# Serial_Load_Cell_converter.net
KiCad netlist of a schematic drawn in EAGLE
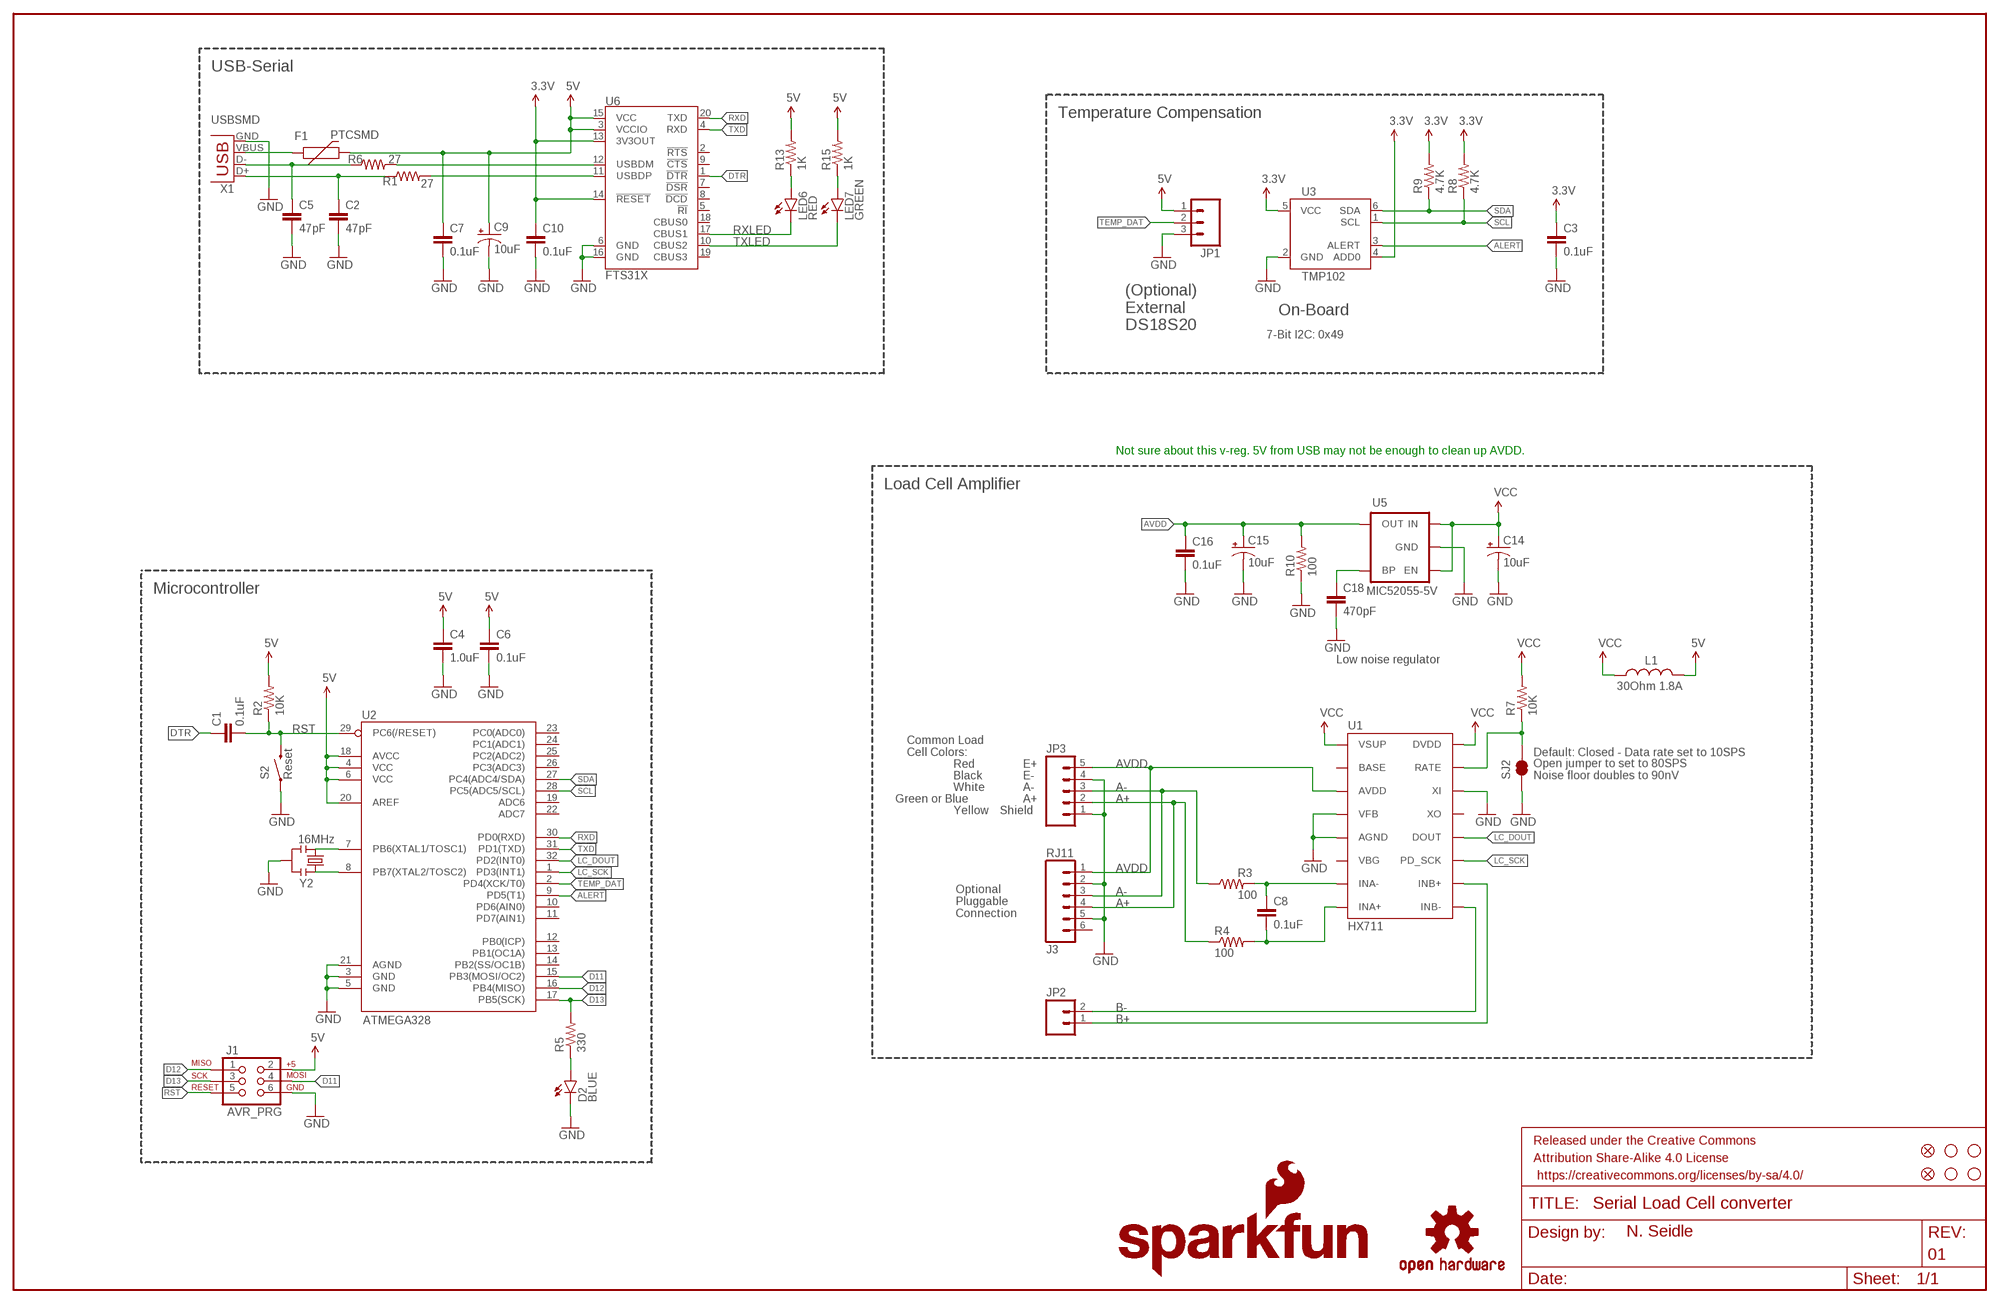
[diagram p0: schematic, sheet 1]

(export (version "E")
  (design (tool "Eeschema 10.0.6"))
  (components
    (comp (ref "C1")
      (value "0.1uF")
      (footprint "eagle-import:0603-CAP")
      (libsource (lib "eagle-import") (part "0.1UF-25V(+80/-20%)(0603)"))
    )
    (comp (ref "C2")
      (value "47pF")
      (footprint "eagle-import:0603-CAP")
      (libsource (lib "eagle-import") (part "47PF-50V-5%(0603)"))
    )
    (comp (ref "C3")
      (value "0.1uF")
      (footprint "eagle-import:0603-CAP")
      (libsource (lib "eagle-import") (part "0.1UF-25V-5%(0603)"))
    )
    (comp (ref "C4")
      (value "1.0uF")
      (footprint "eagle-import:0603-CAP")
      (libsource (lib "eagle-import") (part "1.0UF-16V-10%(0603)"))
    )
    (comp (ref "C5")
      (value "47pF")
      (footprint "eagle-import:0603-CAP")
      (libsource (lib "eagle-import") (part "47PF-50V-5%(0603)"))
    )
    (comp (ref "C6")
      (value "0.1uF")
      (footprint "eagle-import:0603-CAP")
      (libsource (lib "eagle-import") (part "0.1UF-25V(+80/-20%)(0603)"))
    )
    (comp (ref "C7")
      (value "0.1uF")
      (footprint "eagle-import:0603-CAP")
      (libsource (lib "eagle-import") (part "0.1UF-25V(+80/-20%)(0603)"))
    )
    (comp (ref "C8")
      (value "0.1uF")
      (footprint "eagle-import:0603-CAP")
      (libsource (lib "eagle-import") (part "0.1UF-25V-5%(0603)"))
    )
    (comp (ref "C9")
      (value "10uF")
      (footprint "eagle-import:EIA3216")
      (libsource (lib "eagle-import") (part "10UF-16V-10%(TANT)"))
    )
    (comp (ref "C10")
      (value "0.1uF")
      (footprint "eagle-import:0603-CAP")
      (libsource (lib "eagle-import") (part "0.1UF-25V(+80/-20%)(0603)"))
    )
    (comp (ref "C14")
      (value "10uF")
      (footprint "eagle-import:EIA3216")
      (libsource (lib "eagle-import") (part "10UF-16V-10%(TANT)"))
    )
    (comp (ref "C15")
      (value "10uF")
      (footprint "eagle-import:EIA3216")
      (libsource (lib "eagle-import") (part "10UF-16V-10%(TANT)"))
    )
    (comp (ref "C16")
      (value "0.1uF")
      (footprint "eagle-import:0603-CAP")
      (libsource (lib "eagle-import") (part "0.1UF-25V-5%(0603)"))
    )
    (comp (ref "C18")
      (value "470pF")
      (footprint "eagle-import:0603-CAP")
      (libsource (lib "eagle-import") (part "470PF-50V-5%(0603)SMD"))
    )
    (comp (ref "D2")
      (value "BLUE")
      (footprint "eagle-import:LED-1206")
      (libsource (lib "eagle-import") (part "LED-BLUE1206"))
    )
    (comp (ref "F1")
      (value "PTCSMD")
      (footprint "eagle-import:PTC-1206")
      (libsource (lib "eagle-import") (part "PTCSMD"))
    )
    (comp (ref "FID1")
      (value "FIDUCIAL1X2")
      (footprint "eagle-import:FIDUCIAL-1X2")
      (libsource (lib "eagle-import") (part "FIDUCIAL1X2"))
    )
    (comp (ref "FID2")
      (value "FIDUCIAL1X2")
      (footprint "eagle-import:FIDUCIAL-1X2")
      (libsource (lib "eagle-import") (part "FIDUCIAL1X2"))
    )
    (comp (ref "FRAME1")
      (value "FRAME-LEDGER")
      (footprint "eagle-import:CREATIVE_COMMONS")
      (fields (field (name "DESIGNER") "N. Seidle") (field (name "VERSION") "01"))
      (libsource (lib "eagle-import") (part "FRAME-LEDGER"))
    )
    (comp (ref "J1")
      (value "AVR_PRG")
      (footprint "eagle-import:2X3")
      (libsource (lib "eagle-import") (part "AVR_SPI_PRG_6PTH"))
    )
    (comp (ref "J3")
      (value "RJ11")
      (footprint "eagle-import:RJ11-6")
      (libsource (lib "eagle-import") (part "RJ11-6PTH"))
    )
    (comp (ref "JP1")
      (value "M03PTH")
      (footprint "eagle-import:1X03")
      (libsource (lib "eagle-import") (part "M03PTH"))
    )
    (comp (ref "JP2")
      (value "M02PTH")
      (footprint "eagle-import:1X02")
      (libsource (lib "eagle-import") (part "M02PTH"))
    )
    (comp (ref "JP3")
      (value "M05PTH")
      (footprint "eagle-import:1X05")
      (libsource (lib "eagle-import") (part "M05PTH"))
    )
    (comp (ref "L1")
      (value "30Ohm 1.8A")
      (footprint "eagle-import:0603")
      (libsource (lib "eagle-import") (part "INDUCTOR30OHM,1.8A"))
    )
    (comp (ref "LED6")
      (value "RED")
      (footprint "eagle-import:LED-1206")
      (libsource (lib "eagle-import") (part "LED-RED1206"))
    )
    (comp (ref "LED7")
      (value "GREEN")
      (footprint "eagle-import:LED-1206")
      (libsource (lib "eagle-import") (part "LED-GREENLARGE"))
    )
    (comp (ref "LOGO1")
      (value "SFE_LOGO_NAME_FLAME.1_INCH")
      (footprint "eagle-import:SFE_LOGO_NAME_FLAME_.1")
      (libsource (lib "eagle-import") (part "SFE_LOGO_NAME_FLAME.1_INCH"))
    )
    (comp (ref "LOGO2")
      (value "OSHW-LOGOS")
      (footprint "eagle-import:OSHW-LOGO-S")
      (libsource (lib "eagle-import") (part "OSHW-LOGOS"))
    )
    (comp (ref "LOGO4")
      (value "SFE_LOGO_NAME_FLAME.1_INCH")
      (footprint "eagle-import:SFE_LOGO_NAME_FLAME_.1")
      (libsource (lib "eagle-import") (part "SFE_LOGO_NAME_FLAME.1_INCH"))
    )
    (comp (ref "R1")
      (value "27")
      (footprint "eagle-import:0603")
      (libsource (lib "eagle-import") (part "27OHM1/10W1%(0603)"))
    )
    (comp (ref "R2")
      (value "10K")
      (footprint "eagle-import:0603-RES")
      (libsource (lib "eagle-import") (part "10KOHM-1/10W-1%(0603)0603"))
    )
    (comp (ref "R3")
      (value "100")
      (footprint "eagle-import:0603-RES")
      (libsource (lib "eagle-import") (part "100OHM-1/10W-1%(0603)"))
    )
    (comp (ref "R4")
      (value "100")
      (footprint "eagle-import:0603-RES")
      (libsource (lib "eagle-import") (part "100OHM-1/10W-1%(0603)"))
    )
    (comp (ref "R5")
      (value "330")
      (footprint "eagle-import:0603-RES")
      (libsource (lib "eagle-import") (part "330OHM1/10W1%(0603)"))
    )
    (comp (ref "R6")
      (value "27")
      (footprint "eagle-import:0603")
      (libsource (lib "eagle-import") (part "27OHM1/10W1%(0603)"))
    )
    (comp (ref "R7")
      (value "10K")
      (footprint "eagle-import:0603-RES")
      (libsource (lib "eagle-import") (part "10KOHM-1/10W-1%(0603)0603"))
    )
    (comp (ref "R8")
      (value "4.7K")
      (footprint "eagle-import:0603-RES")
      (libsource (lib "eagle-import") (part "4.7KOHM-1/10W-1%(0603)"))
    )
    (comp (ref "R9")
      (value "4.7K")
      (footprint "eagle-import:0603-RES")
      (libsource (lib "eagle-import") (part "4.7KOHM-1/10W-1%(0603)"))
    )
    (comp (ref "R10")
      (value "100")
      (footprint "eagle-import:0603-RES")
      (libsource (lib "eagle-import") (part "100OHM-1/10W-1%(0603)"))
    )
    (comp (ref "R13")
      (value "1K")
      (footprint "eagle-import:0603-RES")
      (libsource (lib "eagle-import") (part "1KOHM-1/10W-1%(0603)"))
    )
    (comp (ref "R15")
      (value "1K")
      (footprint "eagle-import:0603-RES")
      (libsource (lib "eagle-import") (part "1KOHM-1/10W-1%(0603)"))
    )
    (comp (ref "S2")
      (value "Reset")
      (footprint "eagle-import:TACTILE-SWITCH-SMD")
      (libsource (lib "eagle-import") (part "SWITCH-MOMENTARY-2SMD"))
    )
    (comp (ref "SJ2")
      (value "JUMPER-PAD-2-NC_BY_TRACE")
      (footprint "eagle-import:PAD-JUMPER-2-NC_BY_TRACE_YES_SILK")
      (libsource (lib "eagle-import") (part "JUMPER-PAD-2-NC_BY_TRACE"))
    )
    (comp (ref "STANDOFF1")
      (value "STAND-OFF")
      (footprint "eagle-import:STAND-OFF")
      (libsource (lib "eagle-import") (part "STAND-OFF"))
    )
    (comp (ref "STANDOFF2")
      (value "STAND-OFF")
      (footprint "eagle-import:STAND-OFF")
      (libsource (lib "eagle-import") (part "STAND-OFF"))
    )
    (comp (ref "STANDOFF3")
      (value "STAND-OFF")
      (footprint "eagle-import:STAND-OFF")
      (libsource (lib "eagle-import") (part "STAND-OFF"))
    )
    (comp (ref "STANDOFF4")
      (value "STAND-OFF")
      (footprint "eagle-import:STAND-OFF")
      (libsource (lib "eagle-import") (part "STAND-OFF"))
    )
    (comp (ref "U1")
      (value "HX711")
      (footprint "eagle-import:SO16")
      (libsource (lib "eagle-import") (part "HX711HX711"))
    )
    (comp (ref "U2")
      (value "ATMEGA328")
      (footprint "eagle-import:TQFP32-08")
      (libsource (lib "eagle-import") (part "ATMEGA328_SMT"))
    )
    (comp (ref "U3")
      (value "TMP102")
      (footprint "eagle-import:SOT563")
      (libsource (lib "eagle-import") (part "TMP102"))
    )
    (comp (ref "U5")
      (value "MIC52055-5V")
      (footprint "eagle-import:SOT23-5")
      (libsource (lib "eagle-import") (part "MIC52055V"))
    )
    (comp (ref "U6")
      (value "FTS31X")
      (footprint "eagle-import:SSOP20_L")
      (libsource (lib "eagle-import") (part "FT231XS"))
    )
    (comp (ref "X1")
      (value "USBSMD")
      (footprint "eagle-import:USB-MINIB")
      (libsource (lib "eagle-import") (part "USBSMD"))
    )
    (comp (ref "Y2")
      (value "16MHz")
      (footprint "eagle-import:RESONATOR-SMD")
      (libsource (lib "eagle-import") (part "RESONATOR16MHZ"))
    )
  )
  (nets
    (net (code "1") (name "/A+") (class "Default")
      (node (ref "J3") (pin "4") (pinfunction "4_4") (pintype "passive"))
      (node (ref "JP3") (pin "2") (pinfunction "2_2") (pintype "passive"))
      (node (ref "R4") (pin "1") (pinfunction "1_1") (pintype "passive"))
    )
    (net (code "2") (name "/A-") (class "Default")
      (node (ref "J3") (pin "3") (pinfunction "3_3") (pintype "passive"))
      (node (ref "JP3") (pin "3") (pinfunction "3_3") (pintype "passive"))
      (node (ref "R3") (pin "1") (pinfunction "1_1") (pintype "passive"))
    )
    (net (code "3") (name "/B+") (class "Default")
      (node (ref "JP2") (pin "1") (pinfunction "1_1") (pintype "passive"))
      (node (ref "U1") (pin "10") (pinfunction "INB+_10") (pintype "bidirectional"))
    )
    (net (code "4") (name "/B-") (class "Default")
      (node (ref "JP2") (pin "2") (pinfunction "2_2") (pintype "passive"))
      (node (ref "U1") (pin "9") (pinfunction "INB-_9") (pintype "bidirectional"))
    )
    (net (code "5") (name "/RXLED") (class "Default")
      (node (ref "LED6") (pin "C") (pinfunction "C_C") (pintype "passive"))
      (node (ref "U6") (pin "17") (pinfunction "CBUS1_17") (pintype "bidirectional"))
    )
    (net (code "6") (name "/TXLED") (class "Default")
      (node (ref "LED7") (pin "C") (pinfunction "C_C") (pintype "passive"))
      (node (ref "U6") (pin "10") (pinfunction "CBUS2_10") (pintype "bidirectional"))
    )
    (net (code "7") (name "3.3V") (class "Default")
      (node (ref "C10") (pin "1") (pinfunction "1_1") (pintype "passive"))
      (node (ref "C3") (pin "1") (pinfunction "1_1") (pintype "passive"))
      (node (ref "R8") (pin "2") (pinfunction "2_2") (pintype "passive"))
      (node (ref "R9") (pin "2") (pinfunction "2_2") (pintype "passive"))
      (node (ref "U3") (pin "4") (pinfunction "ADD0_4") (pintype "bidirectional"))
      (node (ref "U3") (pin "5") (pinfunction "VCC_5") (pintype "bidirectional"))
      (node (ref "U6") (pin "13") (pinfunction "3V3OUT_13") (pintype "bidirectional"))
      (node (ref "U6") (pin "14") (pinfunction "~{RESET}_14") (pintype "bidirectional"))
    )
    (net (code "8") (name "5V") (class "Default")
      (node (ref "C4") (pin "1") (pinfunction "1_1") (pintype "passive"))
      (node (ref "C6") (pin "1") (pinfunction "1_1") (pintype "passive"))
      (node (ref "C7") (pin "1") (pinfunction "1_1") (pintype "passive"))
      (node (ref "C9") (pin "A") (pinfunction "+_A") (pintype "passive"))
      (node (ref "F1") (pin "2") (pinfunction "2_2") (pintype "bidirectional"))
      (node (ref "J1") (pin "2") (pinfunction "2_2") (pintype "passive"))
      (node (ref "JP1") (pin "1") (pinfunction "1_1") (pintype "passive"))
      (node (ref "L1") (pin "2") (pinfunction "2_2") (pintype "passive"))
      (node (ref "R13") (pin "2") (pinfunction "2_2") (pintype "passive"))
      (node (ref "R15") (pin "2") (pinfunction "2_2") (pintype "passive"))
      (node (ref "R2") (pin "2") (pinfunction "2_2") (pintype "passive"))
      (node (ref "U2") (pin "18") (pinfunction "AVCC_18") (pintype "bidirectional"))
      (node (ref "U2") (pin "20") (pinfunction "AREF_20") (pintype "bidirectional"))
      (node (ref "U2") (pin "4") (pinfunction "VCC_4") (pintype "bidirectional"))
      (node (ref "U2") (pin "6") (pinfunction "VCC_6") (pintype "bidirectional"))
      (node (ref "U6") (pin "15") (pinfunction "VCC_15") (pintype "bidirectional"))
      (node (ref "U6") (pin "3") (pinfunction "VCCIO_3") (pintype "bidirectional"))
    )
    (net (code "9") (name "ALERT") (class "Default")
      (node (ref "U2") (pin "9") (pinfunction "PD5(T1)_9") (pintype "bidirectional"))
      (node (ref "U3") (pin "3") (pinfunction "ALERT_3") (pintype "bidirectional"))
    )
    (net (code "10") (name "AVDD") (class "Default")
      (node (ref "C15") (pin "A") (pinfunction "+_A") (pintype "passive"))
      (node (ref "C16") (pin "1") (pinfunction "1_1") (pintype "passive"))
      (node (ref "J3") (pin "1") (pinfunction "1_1") (pintype "passive"))
      (node (ref "JP3") (pin "5") (pinfunction "5_5") (pintype "passive"))
      (node (ref "R10") (pin "2") (pinfunction "2_2") (pintype "passive"))
      (node (ref "U1") (pin "3") (pinfunction "AVDD_3") (pintype "bidirectional"))
      (node (ref "U5") (pin "5") (pinfunction "OUT_5") (pintype "passive"))
    )
    (net (code "11") (name "D11") (class "Default")
      (node (ref "J1") (pin "4") (pinfunction "4_4") (pintype "passive"))
      (node (ref "U2") (pin "15") (pinfunction "PB3(MOSI/OC2)_15") (pintype "bidirectional"))
    )
    (net (code "12") (name "D12") (class "Default")
      (node (ref "J1") (pin "1") (pinfunction "1_1") (pintype "passive"))
      (node (ref "U2") (pin "16") (pinfunction "PB4(MISO)_16") (pintype "bidirectional"))
    )
    (net (code "13") (name "D13") (class "Default")
      (node (ref "J1") (pin "3") (pinfunction "3_3") (pintype "passive"))
      (node (ref "R5") (pin "2") (pinfunction "2_2") (pintype "passive"))
      (node (ref "U2") (pin "17") (pinfunction "PB5(SCK)_17") (pintype "bidirectional"))
    )
    (net (code "14") (name "DTR") (class "Default")
      (node (ref "C1") (pin "1") (pinfunction "1_1") (pintype "passive"))
      (node (ref "U6") (pin "1") (pinfunction "~{DTR}_1") (pintype "bidirectional"))
    )
    (net (code "15") (name "GND") (class "Default")
      (node (ref "C10") (pin "2") (pinfunction "2_2") (pintype "passive"))
      (node (ref "C14") (pin "C") (pinfunction "-_C") (pintype "passive"))
      (node (ref "C15") (pin "C") (pinfunction "-_C") (pintype "passive"))
      (node (ref "C16") (pin "2") (pinfunction "2_2") (pintype "passive"))
      (node (ref "C18") (pin "2") (pinfunction "2_2") (pintype "passive"))
      (node (ref "C2") (pin "2") (pinfunction "2_2") (pintype "passive"))
      (node (ref "C3") (pin "2") (pinfunction "2_2") (pintype "passive"))
      (node (ref "C4") (pin "2") (pinfunction "2_2") (pintype "passive"))
      (node (ref "C5") (pin "2") (pinfunction "2_2") (pintype "passive"))
      (node (ref "C6") (pin "2") (pinfunction "2_2") (pintype "passive"))
      (node (ref "C7") (pin "2") (pinfunction "2_2") (pintype "passive"))
      (node (ref "C9") (pin "C") (pinfunction "-_C") (pintype "passive"))
      (node (ref "D2") (pin "C") (pinfunction "C_C") (pintype "passive"))
      (node (ref "J1") (pin "6") (pinfunction "6_6") (pintype "passive"))
      (node (ref "J3") (pin "2") (pinfunction "2_2") (pintype "passive"))
      (node (ref "J3") (pin "5") (pinfunction "5_5") (pintype "passive"))
      (node (ref "JP1") (pin "3") (pinfunction "3_3") (pintype "passive"))
      (node (ref "JP3") (pin "1") (pinfunction "1_1") (pintype "passive"))
      (node (ref "JP3") (pin "4") (pinfunction "4_4") (pintype "passive"))
      (node (ref "R10") (pin "1") (pinfunction "1_1") (pintype "passive"))
      (node (ref "S2") (pin "1") (pinfunction "1_1") (pintype "passive"))
      (node (ref "SJ2") (pin "1") (pinfunction "1_1") (pintype "passive"))
      (node (ref "U1") (pin "14") (pinfunction "XI_14") (pintype "bidirectional"))
      (node (ref "U1") (pin "4") (pinfunction "VFB_4") (pintype "bidirectional"))
      (node (ref "U1") (pin "5") (pinfunction "AGND_5") (pintype "bidirectional"))
      (node (ref "U2") (pin "21") (pinfunction "AGND_21") (pintype "bidirectional"))
      (node (ref "U2") (pin "3") (pinfunction "GND_3") (pintype "bidirectional"))
      (node (ref "U2") (pin "5") (pinfunction "GND_5") (pintype "bidirectional"))
      (node (ref "U3") (pin "2") (pinfunction "GND_2") (pintype "bidirectional"))
      (node (ref "U5") (pin "2") (pinfunction "GND_2") (pintype "input"))
      (node (ref "U6") (pin "16") (pinfunction "GND_16") (pintype "bidirectional"))
      (node (ref "U6") (pin "6") (pinfunction "GND_6") (pintype "bidirectional"))
      (node (ref "X1") (pin "GND") (pinfunction "GND_GND") (pintype "bidirectional"))
      (node (ref "Y2") (pin "2") (pinfunction "2_2") (pintype "passive"))
    )
    (net (code "16") (name "LC_DOUT") (class "Default")
      (node (ref "U1") (pin "12") (pinfunction "DOUT_12") (pintype "bidirectional"))
      (node (ref "U2") (pin "32") (pinfunction "PD2(INT0)_32") (pintype "bidirectional"))
    )
    (net (code "17") (name "LC_SCK") (class "Default")
      (node (ref "U1") (pin "11") (pinfunction "PD_SCK_11") (pintype "bidirectional"))
      (node (ref "U2") (pin "1") (pinfunction "PD3(INT1)_1") (pintype "bidirectional"))
    )
    (net (code "18") (name "Net-(C2-Pad1)") (class "Default")
      (node (ref "C2") (pin "1") (pinfunction "1_1") (pintype "passive"))
      (node (ref "R1") (pin "1") (pinfunction "1_1") (pintype "passive"))
      (node (ref "X1") (pin "D+") (pinfunction "D+_D+") (pintype "bidirectional"))
    )
    (net (code "19") (name "Net-(C5-Pad1)") (class "Default")
      (node (ref "C5") (pin "1") (pinfunction "1_1") (pintype "passive"))
      (node (ref "R6") (pin "1") (pinfunction "1_1") (pintype "passive"))
      (node (ref "X1") (pin "D-") (pinfunction "D-_D-") (pintype "bidirectional"))
    )
    (net (code "20") (name "Net-(D2-PadA)") (class "Default")
      (node (ref "D2") (pin "A") (pinfunction "A_A") (pintype "passive"))
      (node (ref "R5") (pin "1") (pinfunction "1_1") (pintype "passive"))
    )
    (net (code "21") (name "Net-(F1-Pad1)") (class "Default")
      (node (ref "F1") (pin "1") (pinfunction "1_1") (pintype "bidirectional"))
      (node (ref "X1") (pin "VBUS") (pinfunction "VBUS_VBUS") (pintype "bidirectional"))
    )
    (net (code "22") (name "Net-(LED6-PadA)") (class "Default")
      (node (ref "LED6") (pin "A") (pinfunction "A_A") (pintype "passive"))
      (node (ref "R13") (pin "1") (pinfunction "1_1") (pintype "passive"))
    )
    (net (code "23") (name "Net-(LED7-PadA)") (class "Default")
      (node (ref "LED7") (pin "A") (pinfunction "A_A") (pintype "passive"))
      (node (ref "R15") (pin "1") (pinfunction "1_1") (pintype "passive"))
    )
    (net (code "24") (name "Net-(U1-INA+)") (class "Default")
      (node (ref "C8") (pin "2") (pinfunction "2_2") (pintype "passive"))
      (node (ref "R4") (pin "2") (pinfunction "2_2") (pintype "passive"))
      (node (ref "U1") (pin "8") (pinfunction "INA+_8") (pintype "bidirectional"))
    )
    (net (code "25") (name "Net-(U1-INA-)") (class "Default")
      (node (ref "C8") (pin "1") (pinfunction "1_1") (pintype "passive"))
      (node (ref "R3") (pin "2") (pinfunction "2_2") (pintype "passive"))
      (node (ref "U1") (pin "7") (pinfunction "INA-_7") (pintype "bidirectional"))
    )
    (net (code "26") (name "Net-(U1-RATE)") (class "Default")
      (node (ref "R7") (pin "1") (pinfunction "1_1") (pintype "passive"))
      (node (ref "SJ2") (pin "2") (pinfunction "2_2") (pintype "passive"))
      (node (ref "U1") (pin "15") (pinfunction "RATE_15") (pintype "bidirectional"))
    )
    (net (code "27") (name "Net-(U2-PB6(XTAL1{slash}TOSC1))") (class "Default")
      (node (ref "U2") (pin "7") (pinfunction "PB6(XTAL1/TOSC1)_7") (pintype "bidirectional"))
      (node (ref "Y2") (pin "1") (pinfunction "1_1") (pintype "passive"))
    )
    (net (code "28") (name "Net-(U2-PB7(XTAL2{slash}TOSC2))") (class "Default")
      (node (ref "U2") (pin "8") (pinfunction "PB7(XTAL2/TOSC2)_8") (pintype "bidirectional"))
      (node (ref "Y2") (pin "3") (pinfunction "3_3") (pintype "passive"))
    )
    (net (code "29") (name "Net-(U5-BP)") (class "Default")
      (node (ref "C18") (pin "1") (pinfunction "1_1") (pintype "passive"))
      (node (ref "U5") (pin "4") (pinfunction "BP_4") (pintype "input"))
    )
    (net (code "30") (name "Net-(U6-USBDM)") (class "Default")
      (node (ref "R6") (pin "2") (pinfunction "2_2") (pintype "passive"))
      (node (ref "U6") (pin "12") (pinfunction "USBDM_12") (pintype "bidirectional"))
    )
    (net (code "31") (name "Net-(U6-USBDP)") (class "Default")
      (node (ref "R1") (pin "2") (pinfunction "2_2") (pintype "passive"))
      (node (ref "U6") (pin "11") (pinfunction "USBDP_11") (pintype "bidirectional"))
    )
    (net (code "32") (name "RST") (class "Default")
      (node (ref "C1") (pin "2") (pinfunction "2_2") (pintype "passive"))
      (node (ref "J1") (pin "5") (pinfunction "5_5") (pintype "passive"))
      (node (ref "R2") (pin "1") (pinfunction "1_1") (pintype "passive"))
      (node (ref "S2") (pin "3") (pinfunction "2_3") (pintype "passive"))
      (node (ref "U2") (pin "29") (pinfunction "PC6(/RESET)_29") (pintype "bidirectional"))
    )
    (net (code "33") (name "RXD") (class "Default")
      (node (ref "U2") (pin "30") (pinfunction "PD0(RXD)_30") (pintype "bidirectional"))
      (node (ref "U6") (pin "20") (pinfunction "TXD_20") (pintype "bidirectional"))
    )
    (net (code "34") (name "SCL") (class "Default")
      (node (ref "R8") (pin "1") (pinfunction "1_1") (pintype "passive"))
      (node (ref "U2") (pin "28") (pinfunction "PC5(ADC5/SCL)_28") (pintype "bidirectional"))
      (node (ref "U3") (pin "1") (pinfunction "SCL_1") (pintype "bidirectional"))
    )
    (net (code "35") (name "SDA") (class "Default")
      (node (ref "R9") (pin "1") (pinfunction "1_1") (pintype "passive"))
      (node (ref "U2") (pin "27") (pinfunction "PC4(ADC4/SDA)_27") (pintype "bidirectional"))
      (node (ref "U3") (pin "6") (pinfunction "SDA_6") (pintype "bidirectional"))
    )
    (net (code "36") (name "TEMP_DAT") (class "Default")
      (node (ref "JP1") (pin "2") (pinfunction "2_2") (pintype "passive"))
      (node (ref "U2") (pin "2") (pinfunction "PD4(XCK/T0)_2") (pintype "bidirectional"))
    )
    (net (code "37") (name "TXD") (class "Default")
      (node (ref "U2") (pin "31") (pinfunction "PD1(TXD)_31") (pintype "bidirectional"))
      (node (ref "U6") (pin "4") (pinfunction "RXD_4") (pintype "bidirectional"))
    )
    (net (code "38") (name "VCC") (class "Default")
      (node (ref "C14") (pin "A") (pinfunction "+_A") (pintype "passive"))
      (node (ref "L1") (pin "1") (pinfunction "1_1") (pintype "passive"))
      (node (ref "R7") (pin "2") (pinfunction "2_2") (pintype "passive"))
      (node (ref "U1") (pin "1") (pinfunction "VSUP_1") (pintype "bidirectional"))
      (node (ref "U1") (pin "16") (pinfunction "DVDD_16") (pintype "bidirectional"))
      (node (ref "U5") (pin "1") (pinfunction "IN_1") (pintype "input"))
      (node (ref "U5") (pin "3") (pinfunction "EN_3") (pintype "input"))
    )
    (net (code "39") (name "unconnected-(J3-Pad6)") (class "Default")
      (node (ref "J3") (pin "6") (pinfunction "6_6") (pintype "passive"))
    )
    (net (code "40") (name "unconnected-(U1-BASE-Pad2)") (class "Default")
      (node (ref "U1") (pin "2") (pinfunction "BASE_2") (pintype "bidirectional"))
    )
    (net (code "41") (name "unconnected-(U1-VBG-Pad6)") (class "Default")
      (node (ref "U1") (pin "6") (pinfunction "VBG_6") (pintype "bidirectional"))
    )
    (net (code "42") (name "unconnected-(U1-XO-Pad13)") (class "Default")
      (node (ref "U1") (pin "13") (pinfunction "XO_13") (pintype "bidirectional"))
    )
    (net (code "43") (name "unconnected-(U2-ADC6-Pad19)") (class "Default")
      (node (ref "U2") (pin "19") (pinfunction "ADC6_19") (pintype "bidirectional"))
    )
    (net (code "44") (name "unconnected-(U2-ADC7-Pad22)") (class "Default")
      (node (ref "U2") (pin "22") (pinfunction "ADC7_22") (pintype "bidirectional"))
    )
    (net (code "45") (name "unconnected-(U2-PB0(ICP)-Pad12)") (class "Default")
      (node (ref "U2") (pin "12") (pinfunction "PB0(ICP)_12") (pintype "bidirectional"))
    )
    (net (code "46") (name "unconnected-(U2-PB1(OC1A)-Pad13)") (class "Default")
      (node (ref "U2") (pin "13") (pinfunction "PB1(OC1A)_13") (pintype "bidirectional"))
    )
    (net (code "47") (name "unconnected-(U2-PB2(SS{slash}OC1B)-Pad14)") (class "Default")
      (node (ref "U2") (pin "14") (pinfunction "PB2(SS/OC1B)_14") (pintype "bidirectional"))
    )
    (net (code "48") (name "unconnected-(U2-PC0(ADC0)-Pad23)") (class "Default")
      (node (ref "U2") (pin "23") (pinfunction "PC0(ADC0)_23") (pintype "bidirectional"))
    )
    (net (code "49") (name "unconnected-(U2-PC1(ADC1)-Pad24)") (class "Default")
      (node (ref "U2") (pin "24") (pinfunction "PC1(ADC1)_24") (pintype "bidirectional"))
    )
    (net (code "50") (name "unconnected-(U2-PC2(ADC2)-Pad25)") (class "Default")
      (node (ref "U2") (pin "25") (pinfunction "PC2(ADC2)_25") (pintype "bidirectional"))
    )
    (net (code "51") (name "unconnected-(U2-PC3(ADC3)-Pad26)") (class "Default")
      (node (ref "U2") (pin "26") (pinfunction "PC3(ADC3)_26") (pintype "bidirectional"))
    )
    (net (code "52") (name "unconnected-(U2-PD6(AIN0)-Pad10)") (class "Default")
      (node (ref "U2") (pin "10") (pinfunction "PD6(AIN0)_10") (pintype "bidirectional"))
    )
    (net (code "53") (name "unconnected-(U2-PD7(AIN1)-Pad11)") (class "Default")
      (node (ref "U2") (pin "11") (pinfunction "PD7(AIN1)_11") (pintype "bidirectional"))
    )
    (net (code "54") (name "unconnected-(U6-CBUS0-Pad18)") (class "Default")
      (node (ref "U6") (pin "18") (pinfunction "CBUS0_18") (pintype "bidirectional"))
    )
    (net (code "55") (name "unconnected-(U6-CBUS3-Pad19)") (class "Default")
      (node (ref "U6") (pin "19") (pinfunction "CBUS3_19") (pintype "bidirectional"))
    )
    (net (code "56") (name "unconnected-(U6-~{CTS}-Pad9)") (class "Default")
      (node (ref "U6") (pin "9") (pinfunction "~{CTS}_9") (pintype "bidirectional"))
    )
    (net (code "57") (name "unconnected-(U6-~{DCD}-Pad8)") (class "Default")
      (node (ref "U6") (pin "8") (pinfunction "~{DCD}_8") (pintype "bidirectional"))
    )
    (net (code "58") (name "unconnected-(U6-~{DSR}-Pad7)") (class "Default")
      (node (ref "U6") (pin "7") (pinfunction "~{DSR}_7") (pintype "bidirectional"))
    )
    (net (code "59") (name "unconnected-(U6-~{RI}-Pad5)") (class "Default")
      (node (ref "U6") (pin "5") (pinfunction "~{RI}_5") (pintype "bidirectional"))
    )
    (net (code "60") (name "unconnected-(U6-~{RTS}-Pad2)") (class "Default")
      (node (ref "U6") (pin "2") (pinfunction "~{RTS}_2") (pintype "bidirectional"))
    )
  )
)
